# DM3370_Connector_A.net
KiCad netlist of a schematic drawn in Altium Designer
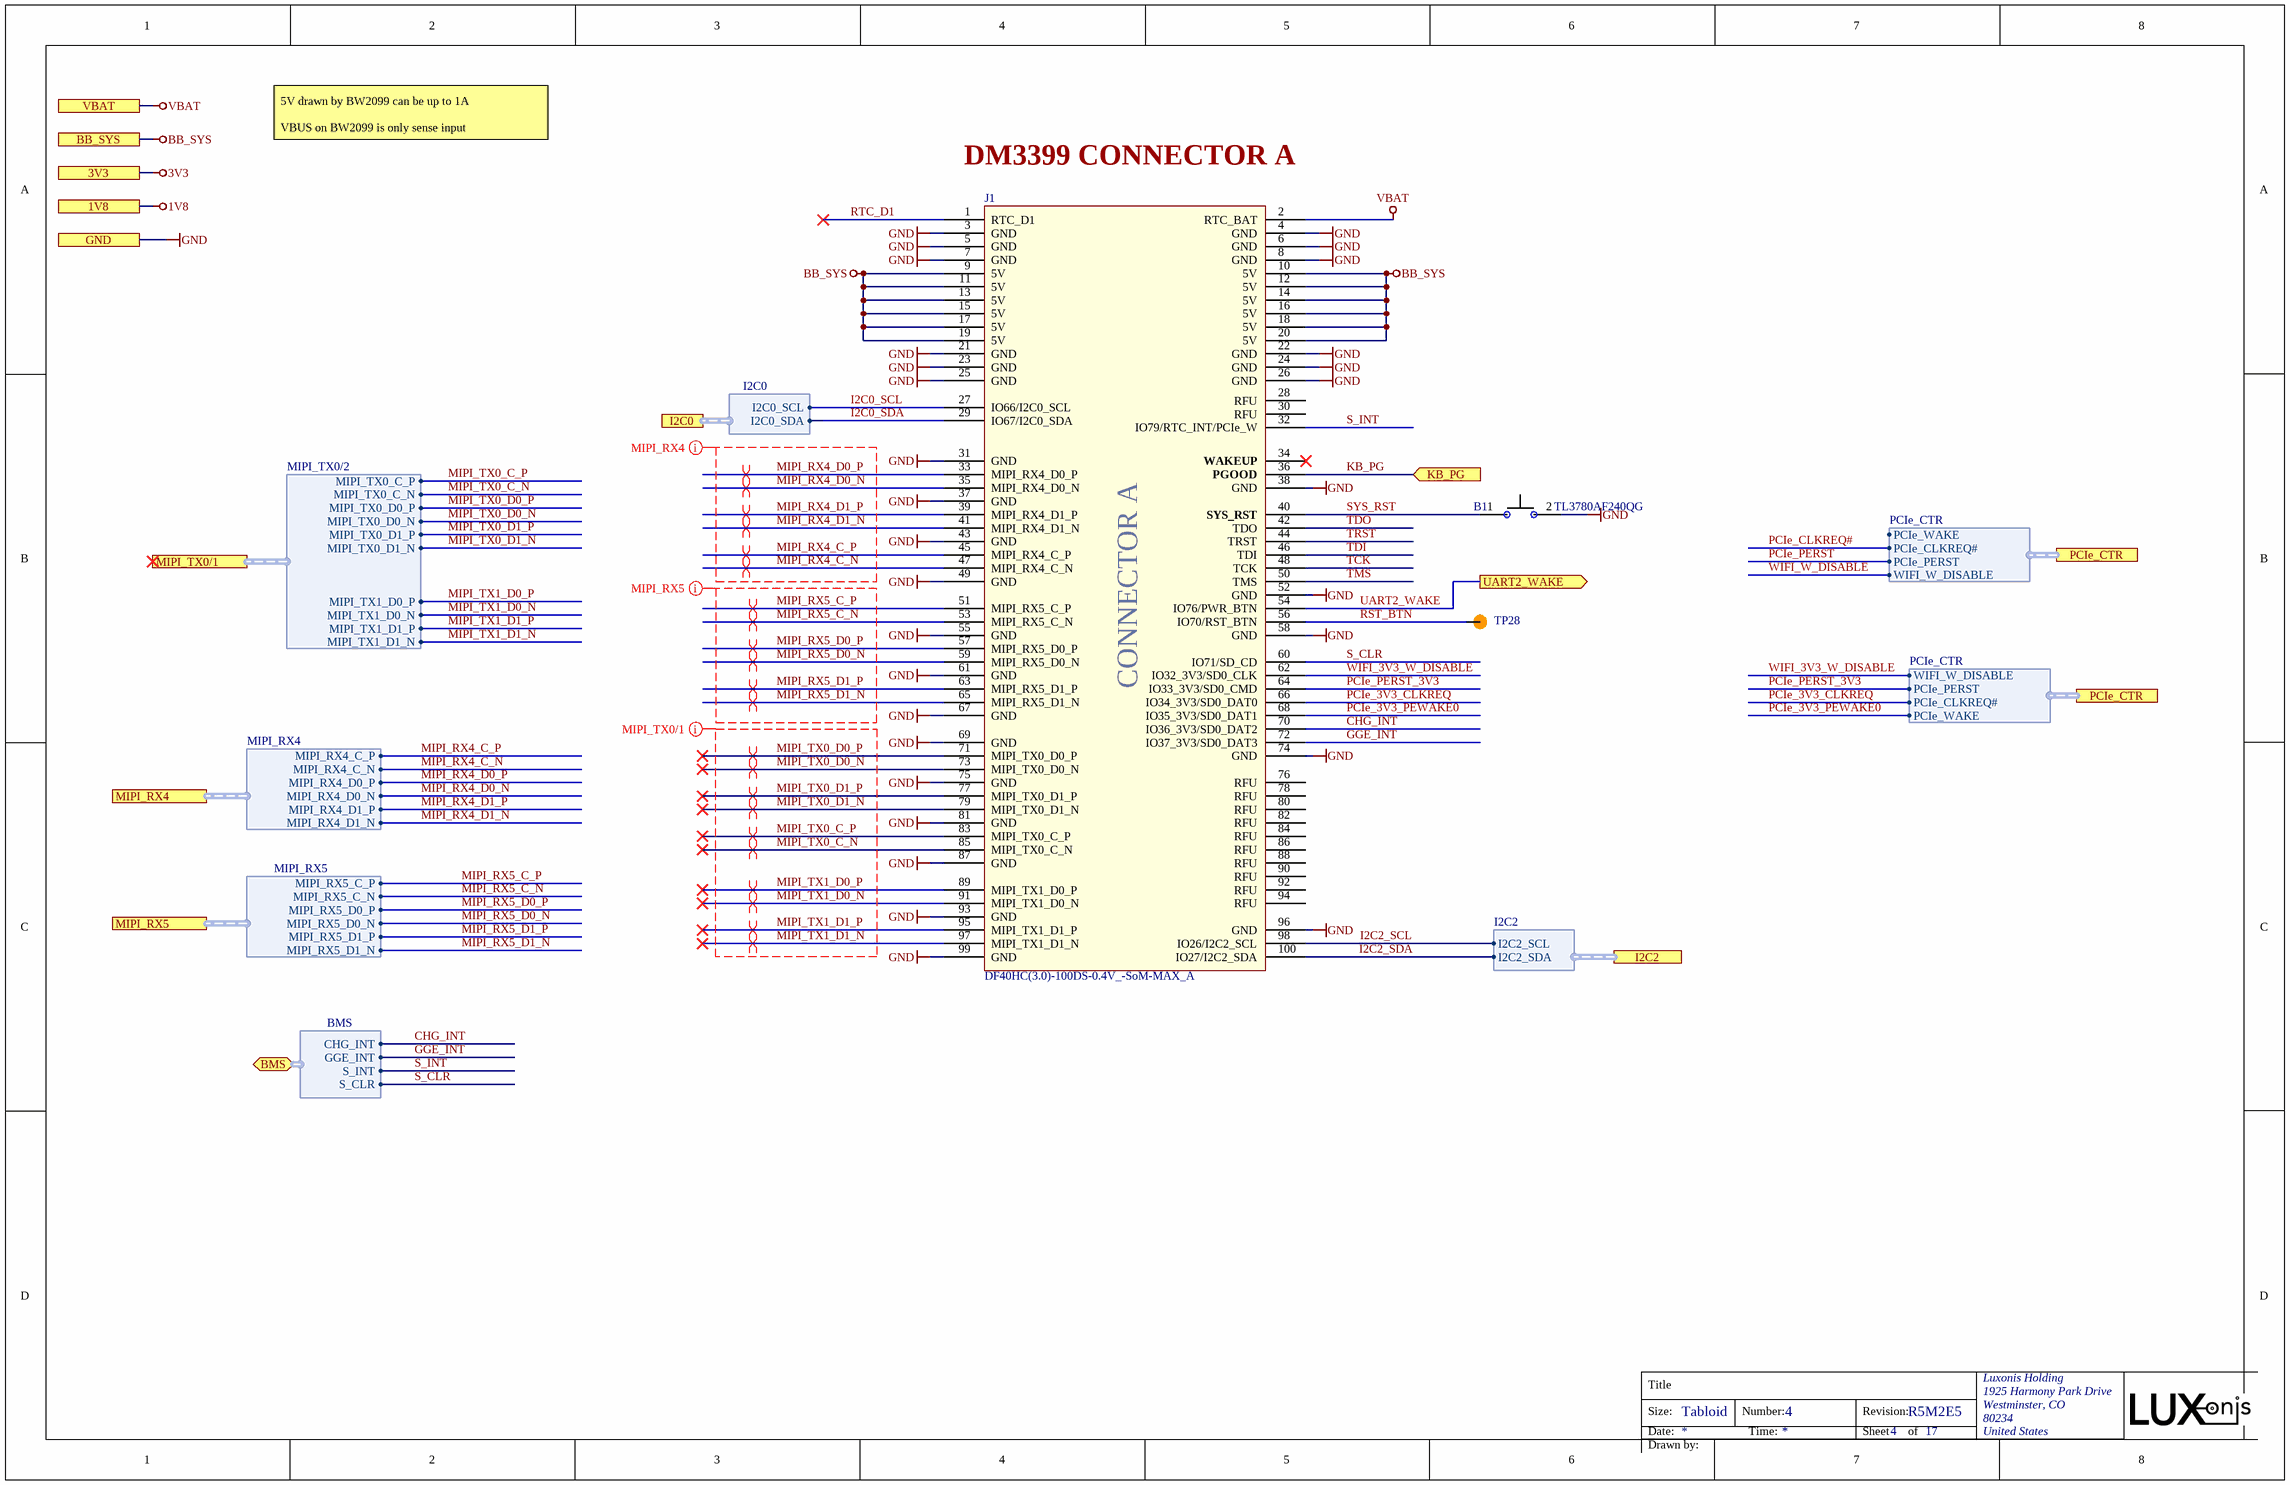
[diagram p0: DM3370_Connector_A.SchDoc]

(export (version "E")
  (design (tool "Eeschema 10.0.6"))
  (components
    (comp (ref "B1")
      (value "TL3780AF240QG")
      (footprint "TL3780AF240QG-Footprint-1")
      (libsource (lib "Luxonis LLC") (part "TL3780AF240QG"))
    )
    (comp (ref "J1")
      (value "DF40HC(3.0)-100DS-0.4V_-SoM-MAX_A")
      (footprint "SOM_MAX_CONN_A_DF40HC-3.0-100DS-0.4V_minpad")
      (description "OAK-SoM-MAX base board conn. A")
      (fields (field (name "SOURCE") "LuxonisMaster_nejc.SchLib"))
      (libsource (lib "Luxonis LLC") (part "DF40HC(3.0)-100DS-0.4V_-SoM-MAX_A"))
    )
    (comp (ref "TP28")
      (value "TEST_POINT")
      (footprint "TP075_150_NS")
      (libsource (lib "Luxonis LLC") (part "TEST_POINT"))
    )
  )
  (nets
    (net (code "8") (name "/CHG_INT") (class "Default")
      (node (ref "J1") (pin "70") (pinfunction "IO36_3V3/SD0_DAT2_70") (pintype "passive"))
    )
    (net (code "9") (name "/GGE_INT") (class "Default")
      (node (ref "J1") (pin "72") (pinfunction "IO37_3V3/SD0_DAT3_72") (pintype "passive"))
    )
    (net (code "10") (name "/I2C0_SCL") (class "Default")
      (node (ref "J1") (pin "27") (pinfunction "IO66/I2C0_SCL_27") (pintype "passive"))
    )
    (net (code "11") (name "/I2C0_SDA") (class "Default")
      (node (ref "J1") (pin "29") (pinfunction "IO67/I2C0_SDA_29") (pintype "passive"))
    )
    (net (code "12") (name "/I2C2_SCL") (class "Default")
      (node (ref "J1") (pin "98") (pinfunction "IO26/I2C2_SCL_98") (pintype "passive"))
    )
    (net (code "13") (name "/I2C2_SDA") (class "Default")
      (node (ref "J1") (pin "100") (pinfunction "IO27/I2C2_SDA_100") (pintype "passive"))
    )
    (net (code "14") (name "/KB_PG") (class "Default")
      (node (ref "J1") (pin "36") (pinfunction "PGOOD_36") (pintype "passive"))
    )
    (net (code "15") (name "/MIPI_RX4_C_N") (class "Default")
      (node (ref "J1") (pin "47") (pinfunction "MIPI_RX4_C_N_47") (pintype "passive"))
    )
    (net (code "16") (name "/MIPI_RX4_C_P") (class "Default")
      (node (ref "J1") (pin "45") (pinfunction "MIPI_RX4_C_P_45") (pintype "passive"))
    )
    (net (code "17") (name "/MIPI_RX4_D0_N") (class "Default")
      (node (ref "J1") (pin "35") (pinfunction "MIPI_RX4_D0_N_35") (pintype "passive"))
    )
    (net (code "18") (name "/MIPI_RX4_D0_P") (class "Default")
      (node (ref "J1") (pin "33") (pinfunction "MIPI_RX4_D0_P_33") (pintype "passive"))
    )
    (net (code "19") (name "/MIPI_RX4_D1_N") (class "Default")
      (node (ref "J1") (pin "41") (pinfunction "MIPI_RX4_D1_N_41") (pintype "passive"))
    )
    (net (code "20") (name "/MIPI_RX4_D1_P") (class "Default")
      (node (ref "J1") (pin "39") (pinfunction "MIPI_RX4_D1_P_39") (pintype "passive"))
    )
    (net (code "21") (name "/MIPI_RX5_C_N") (class "Default")
      (node (ref "J1") (pin "53") (pinfunction "MIPI_RX5_C_N_53") (pintype "passive"))
    )
    (net (code "22") (name "/MIPI_RX5_C_P") (class "Default")
      (node (ref "J1") (pin "51") (pinfunction "MIPI_RX5_C_P_51") (pintype "passive"))
    )
    (net (code "23") (name "/MIPI_RX5_D0_N") (class "Default")
      (node (ref "J1") (pin "59") (pinfunction "MIPI_RX5_D0_N_59") (pintype "passive"))
    )
    (net (code "24") (name "/MIPI_RX5_D0_P") (class "Default")
      (node (ref "J1") (pin "57") (pinfunction "MIPI_RX5_D0_P_57") (pintype "passive"))
    )
    (net (code "25") (name "/MIPI_RX5_D1_N") (class "Default")
      (node (ref "J1") (pin "65") (pinfunction "MIPI_RX5_D1_N_65") (pintype "passive"))
    )
    (net (code "26") (name "/MIPI_RX5_D1_P") (class "Default")
      (node (ref "J1") (pin "63") (pinfunction "MIPI_RX5_D1_P_63") (pintype "passive"))
    )
    (net (code "27") (name "/MIPI_TX0_C_N") (class "Default")
      (node (ref "J1") (pin "85") (pinfunction "MIPI_TX0_C_N_85") (pintype "passive+no_connect"))
    )
    (net (code "28") (name "/MIPI_TX0_C_P") (class "Default")
      (node (ref "J1") (pin "83") (pinfunction "MIPI_TX0_C_P_83") (pintype "passive+no_connect"))
    )
    (net (code "29") (name "/MIPI_TX0_D0_N") (class "Default")
      (node (ref "J1") (pin "73") (pinfunction "MIPI_TX0_D0_N_73") (pintype "passive+no_connect"))
    )
    (net (code "30") (name "/MIPI_TX0_D0_P") (class "Default")
      (node (ref "J1") (pin "71") (pinfunction "MIPI_TX0_D0_P_71") (pintype "passive+no_connect"))
    )
    (net (code "31") (name "/MIPI_TX0_D1_N") (class "Default")
      (node (ref "J1") (pin "79") (pinfunction "MIPI_TX0_D1_N_79") (pintype "passive+no_connect"))
    )
    (net (code "32") (name "/MIPI_TX0_D1_P") (class "Default")
      (node (ref "J1") (pin "77") (pinfunction "MIPI_TX0_D1_P_77") (pintype "passive+no_connect"))
    )
    (net (code "33") (name "/MIPI_TX1_D0_N") (class "Default")
      (node (ref "J1") (pin "91") (pinfunction "MIPI_TX1_D0_N_91") (pintype "passive+no_connect"))
    )
    (net (code "34") (name "/MIPI_TX1_D0_P") (class "Default")
      (node (ref "J1") (pin "89") (pinfunction "MIPI_TX1_D0_P_89") (pintype "passive+no_connect"))
    )
    (net (code "35") (name "/MIPI_TX1_D1_N") (class "Default")
      (node (ref "J1") (pin "97") (pinfunction "MIPI_TX1_D1_N_97") (pintype "passive+no_connect"))
    )
    (net (code "36") (name "/MIPI_TX1_D1_P") (class "Default")
      (node (ref "J1") (pin "95") (pinfunction "MIPI_TX1_D1_P_95") (pintype "passive+no_connect"))
    )
    (net (code "37") (name "/PCIe_3V3_CLKREQ") (class "Default")
      (node (ref "J1") (pin "66") (pinfunction "IO34_3V3/SD0_DAT0_66") (pintype "passive"))
    )
    (net (code "38") (name "/PCIe_3V3_PEWAKE0") (class "Default")
      (node (ref "J1") (pin "68") (pinfunction "IO35_3V3/SD0_DAT1_68") (pintype "passive"))
    )
    (net (code "41") (name "/PCIe_PERST_3V3") (class "Default")
      (node (ref "J1") (pin "64") (pinfunction "IO33_3V3/SD0_CMD_64") (pintype "passive"))
    )
    (net (code "42") (name "/RST_BTN") (class "Default")
      (node (ref "J1") (pin "56") (pinfunction "IO70/RST_BTN_56") (pintype "passive"))
      (node (ref "TP28") (pin "1") (pintype "passive"))
    )
    (net (code "43") (name "/RTC_D1") (class "Default")
      (node (ref "J1") (pin "1") (pinfunction "RTC_D1_1") (pintype "passive+no_connect"))
    )
    (net (code "44") (name "/SYS_RST") (class "Default")
      (node (ref "B1") (pin "1") (pinfunction "1_1") (pintype "passive"))
      (node (ref "J1") (pin "40") (pinfunction "SYS_RST_40") (pintype "passive"))
    )
    (net (code "45") (name "/S_CLR") (class "Default")
      (node (ref "J1") (pin "60") (pinfunction "IO71/SD_CD_60") (pintype "passive"))
    )
    (net (code "46") (name "/S_INT") (class "Default")
      (node (ref "J1") (pin "32") (pinfunction "IO79/RTC_INT/PCIe_W_32") (pintype "passive"))
    )
    (net (code "47") (name "/TCK") (class "Default")
      (node (ref "J1") (pin "48") (pinfunction "TCK_48") (pintype "passive"))
    )
    (net (code "48") (name "/TDI") (class "Default")
      (node (ref "J1") (pin "46") (pinfunction "TDI_46") (pintype "passive"))
    )
    (net (code "49") (name "/TDO") (class "Default")
      (node (ref "J1") (pin "42") (pinfunction "TDO_42") (pintype "passive"))
    )
    (net (code "50") (name "/TMS") (class "Default")
      (node (ref "J1") (pin "50") (pinfunction "TMS_50") (pintype "passive"))
    )
    (net (code "51") (name "/TRST") (class "Default")
      (node (ref "J1") (pin "44") (pinfunction "TRST_44") (pintype "passive"))
    )
    (net (code "52") (name "/UART2_WAKE") (class "Default")
      (node (ref "J1") (pin "54") (pinfunction "IO76/PWR_BTN_54") (pintype "passive"))
    )
    (net (code "53") (name "/WIFI_3V3_W_DISABLE") (class "Default")
      (node (ref "J1") (pin "62") (pinfunction "IO32_3V3/SD0_CLK_62") (pintype "passive"))
    )
    (net (code "64") (name "BB_SYS") (class "Default")
      (node (ref "J1") (pin "10") (pinfunction "5V_10") (pintype "passive"))
      (node (ref "J1") (pin "11") (pinfunction "5V_11") (pintype "passive"))
      (node (ref "J1") (pin "12") (pinfunction "5V_12") (pintype "passive"))
      (node (ref "J1") (pin "13") (pinfunction "5V_13") (pintype "passive"))
      (node (ref "J1") (pin "14") (pinfunction "5V_14") (pintype "passive"))
      (node (ref "J1") (pin "15") (pinfunction "5V_15") (pintype "passive"))
      (node (ref "J1") (pin "16") (pinfunction "5V_16") (pintype "passive"))
      (node (ref "J1") (pin "17") (pinfunction "5V_17") (pintype "passive"))
      (node (ref "J1") (pin "18") (pinfunction "5V_18") (pintype "passive"))
      (node (ref "J1") (pin "19") (pinfunction "5V_19") (pintype "passive"))
      (node (ref "J1") (pin "20") (pinfunction "5V_20") (pintype "passive"))
      (node (ref "J1") (pin "9") (pinfunction "5V_9") (pintype "passive"))
    )
    (net (code "65") (name "GND") (class "Default")
      (node (ref "B1") (pin "2") (pinfunction "2_2") (pintype "passive"))
      (node (ref "J1") (pin "21") (pinfunction "GND_21") (pintype "passive"))
      (node (ref "J1") (pin "22") (pinfunction "GND_22") (pintype "passive"))
      (node (ref "J1") (pin "23") (pinfunction "GND_23") (pintype "passive"))
      (node (ref "J1") (pin "24") (pinfunction "GND_24") (pintype "passive"))
      (node (ref "J1") (pin "25") (pinfunction "GND_25") (pintype "passive"))
      (node (ref "J1") (pin "26") (pinfunction "GND_26") (pintype "passive"))
      (node (ref "J1") (pin "3") (pinfunction "GND_3") (pintype "passive"))
      (node (ref "J1") (pin "31") (pinfunction "GND_31") (pintype "passive"))
      (node (ref "J1") (pin "37") (pinfunction "GND_37") (pintype "passive"))
      (node (ref "J1") (pin "38") (pinfunction "GND_38") (pintype "passive"))
      (node (ref "J1") (pin "4") (pinfunction "GND_4") (pintype "passive"))
      (node (ref "J1") (pin "43") (pinfunction "GND_43") (pintype "passive"))
      (node (ref "J1") (pin "49") (pinfunction "GND_49") (pintype "passive"))
      (node (ref "J1") (pin "5") (pinfunction "GND_5") (pintype "passive"))
      (node (ref "J1") (pin "52") (pinfunction "GND_52") (pintype "passive"))
      (node (ref "J1") (pin "55") (pinfunction "GND_55") (pintype "passive"))
      (node (ref "J1") (pin "58") (pinfunction "GND_58") (pintype "passive"))
      (node (ref "J1") (pin "6") (pinfunction "GND_6") (pintype "passive"))
      (node (ref "J1") (pin "61") (pinfunction "GND_61") (pintype "passive"))
      (node (ref "J1") (pin "67") (pinfunction "GND_67") (pintype "passive"))
      (node (ref "J1") (pin "69") (pinfunction "GND_69") (pintype "passive"))
      (node (ref "J1") (pin "7") (pinfunction "GND_7") (pintype "passive"))
      (node (ref "J1") (pin "74") (pinfunction "GND_74") (pintype "passive"))
      (node (ref "J1") (pin "75") (pinfunction "GND_75") (pintype "passive"))
      (node (ref "J1") (pin "8") (pinfunction "GND_8") (pintype "passive"))
      (node (ref "J1") (pin "81") (pinfunction "GND_81") (pintype "passive"))
      (node (ref "J1") (pin "87") (pinfunction "GND_87") (pintype "passive"))
      (node (ref "J1") (pin "93") (pinfunction "GND_93") (pintype "passive"))
      (node (ref "J1") (pin "96") (pinfunction "GND_96") (pintype "passive"))
      (node (ref "J1") (pin "99") (pinfunction "GND_99") (pintype "passive"))
    )
    (net (code "66") (name "VBAT") (class "Default")
      (node (ref "J1") (pin "2") (pinfunction "RTC_BAT_2") (pintype "passive"))
    )
    (net (code "67") (name "unconnected-(J1-RFU-Pad28)") (class "Default")
      (node (ref "J1") (pin "28") (pinfunction "RFU_28") (pintype "passive"))
    )
    (net (code "68") (name "unconnected-(J1-RFU-Pad30)") (class "Default")
      (node (ref "J1") (pin "30") (pinfunction "RFU_30") (pintype "passive"))
    )
    (net (code "69") (name "unconnected-(J1-RFU-Pad76)") (class "Default")
      (node (ref "J1") (pin "76") (pinfunction "RFU_76") (pintype "passive"))
    )
    (net (code "70") (name "unconnected-(J1-RFU-Pad78)") (class "Default")
      (node (ref "J1") (pin "78") (pinfunction "RFU_78") (pintype "passive"))
    )
    (net (code "71") (name "unconnected-(J1-RFU-Pad80)") (class "Default")
      (node (ref "J1") (pin "80") (pinfunction "RFU_80") (pintype "passive"))
    )
    (net (code "72") (name "unconnected-(J1-RFU-Pad82)") (class "Default")
      (node (ref "J1") (pin "82") (pinfunction "RFU_82") (pintype "passive"))
    )
    (net (code "73") (name "unconnected-(J1-RFU-Pad84)") (class "Default")
      (node (ref "J1") (pin "84") (pinfunction "RFU_84") (pintype "passive"))
    )
    (net (code "74") (name "unconnected-(J1-RFU-Pad86)") (class "Default")
      (node (ref "J1") (pin "86") (pinfunction "RFU_86") (pintype "passive"))
    )
    (net (code "75") (name "unconnected-(J1-RFU-Pad88)") (class "Default")
      (node (ref "J1") (pin "88") (pinfunction "RFU_88") (pintype "passive"))
    )
    (net (code "76") (name "unconnected-(J1-RFU-Pad90)") (class "Default")
      (node (ref "J1") (pin "90") (pinfunction "RFU_90") (pintype "passive"))
    )
    (net (code "77") (name "unconnected-(J1-RFU-Pad92)") (class "Default")
      (node (ref "J1") (pin "92") (pinfunction "RFU_92") (pintype "passive"))
    )
    (net (code "78") (name "unconnected-(J1-RFU-Pad94)") (class "Default")
      (node (ref "J1") (pin "94") (pinfunction "RFU_94") (pintype "passive"))
    )
    (net (code "79") (name "unconnected-(J1-WAKEUP-Pad34)") (class "Default")
      (node (ref "J1") (pin "34") (pinfunction "WAKEUP_34") (pintype "passive+no_connect"))
    )
  )
)
